# LPDDR4_SDRAM_-_1.net
KiCad netlist of a schematic drawn in Altium Designer
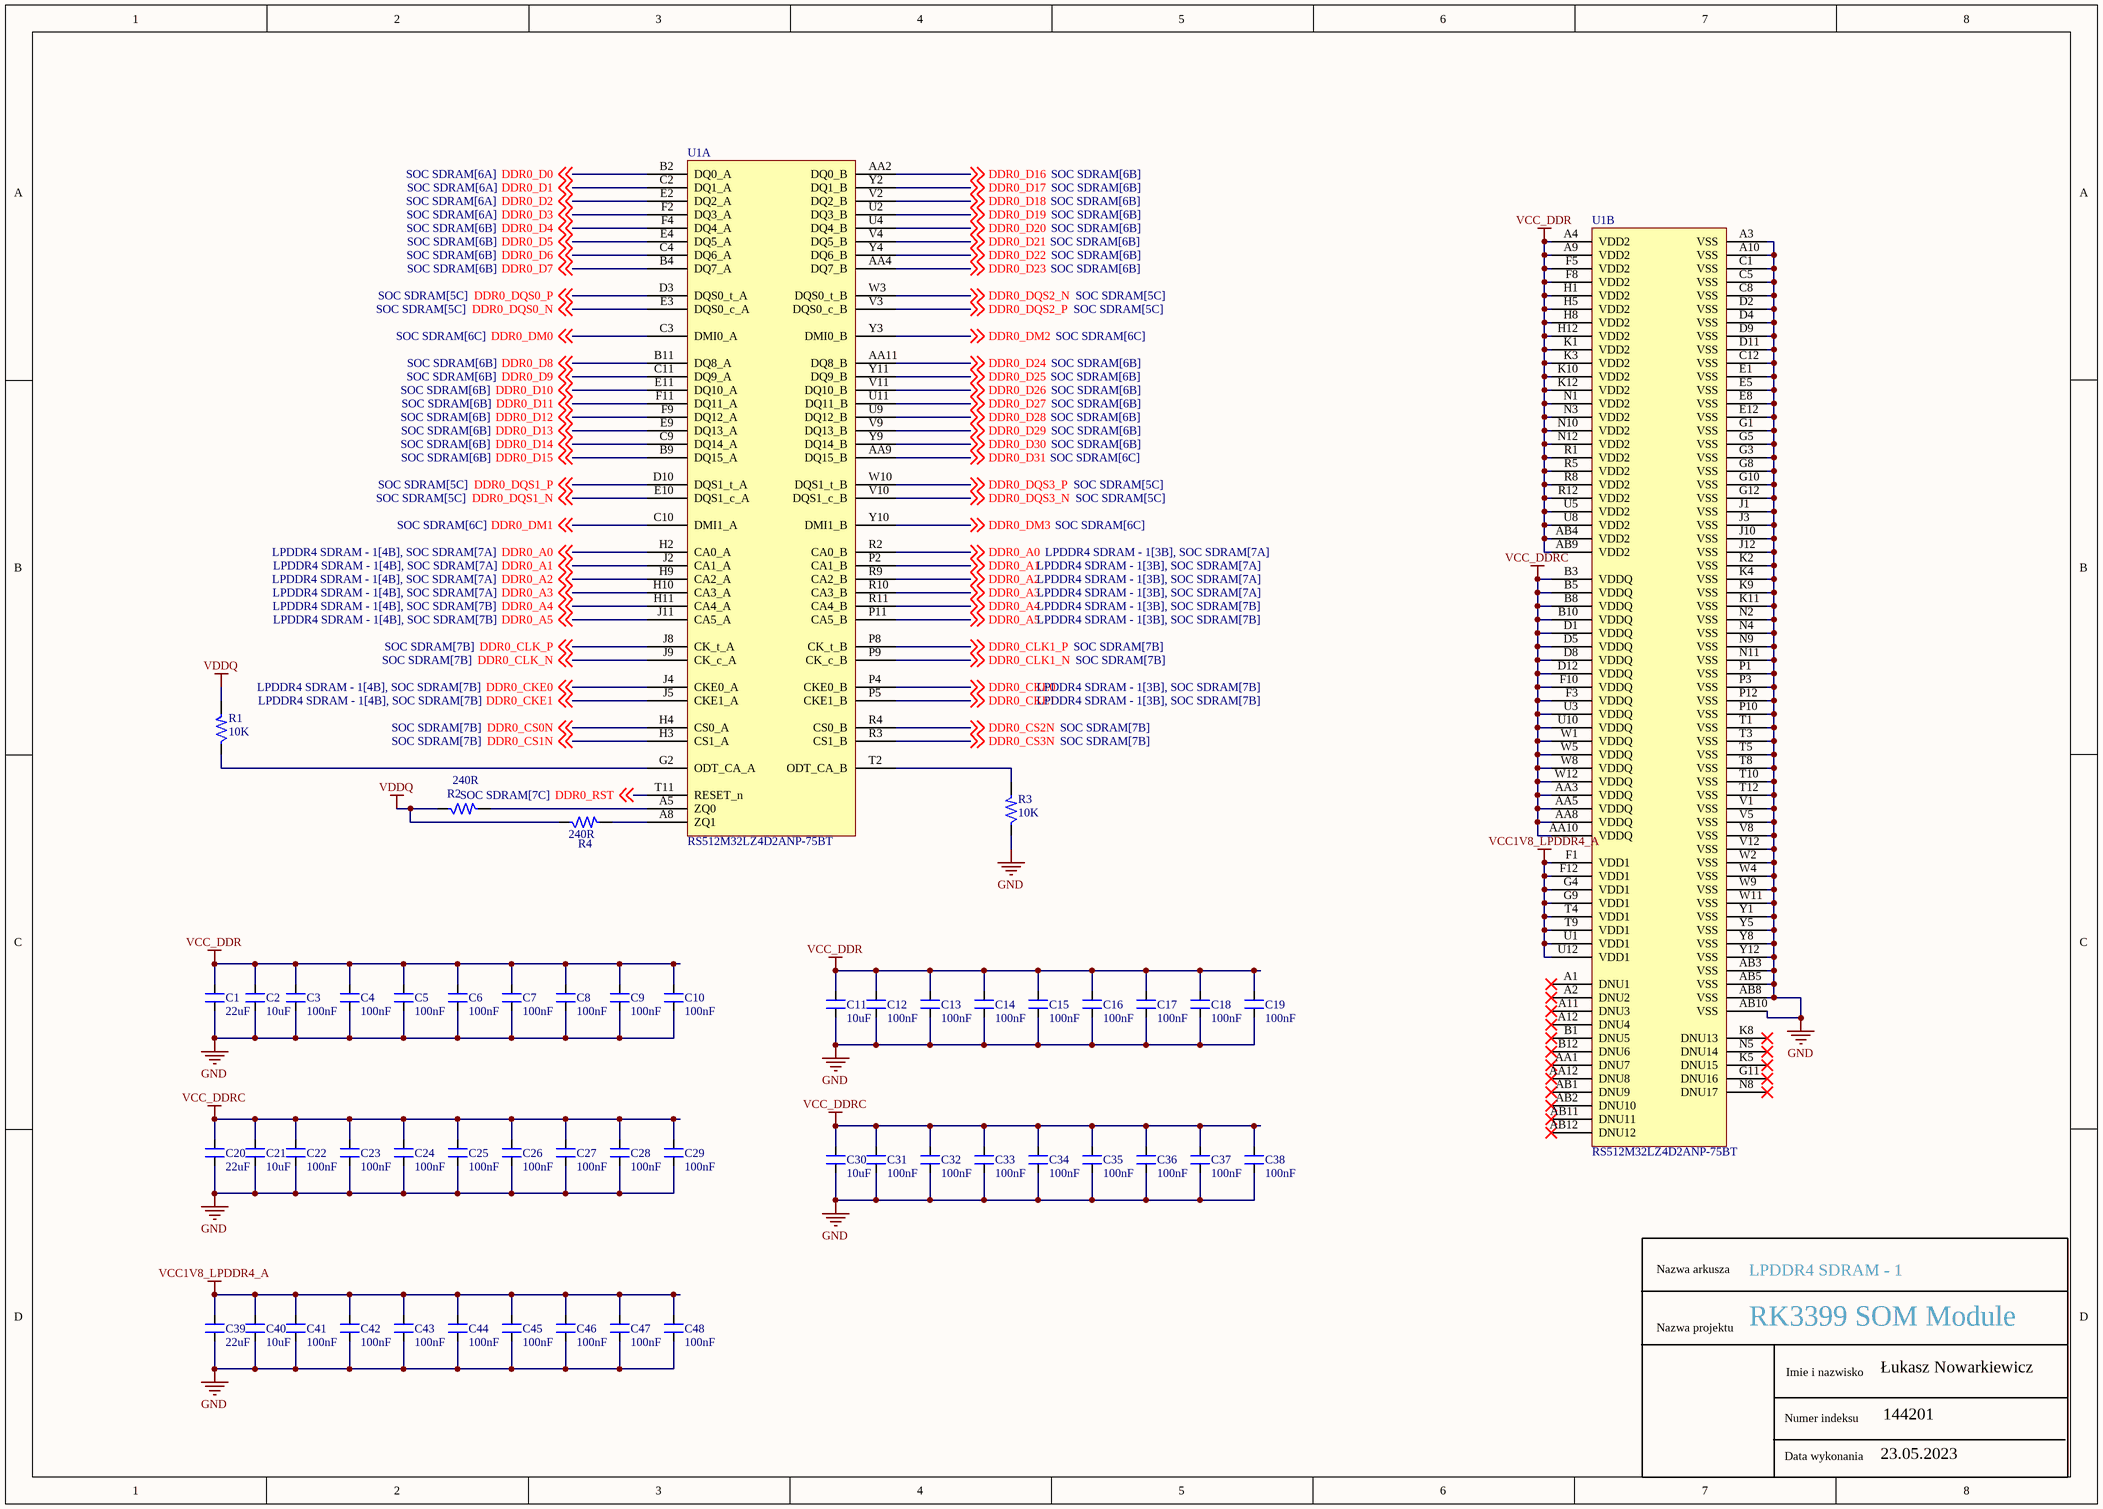
[diagram p0: LPDDR4 SDRAM - 1.SchDoc]

(export (version "E")
  (design (tool "Eeschema 10.0.6"))
  (components
    (comp (ref "C1")
      (value "22uF")
      (footprint "CAP_0603")
      (description "22µF ±20% 10V Ceramic Capacitor X5R 0603 (1608 Metric)")
      (fields
        (field (name "MANUFACTURER") "Murata Electronics")
        (field (name "MANUFACTURER PART NUMBER") "GRM188R61A226ME15D")
      )
      (libsource (lib "EsteemPCB_SOM_Course_intlib") (part "CAP_22uF-10V-20%-0603"))
    )
    (comp (ref "C2")
      (value "10uF")
      (footprint "CAP_0603")
      (description "10µF ±10% 10V Ceramic Capacitor X5R 0603 (1608 Metric)")
      (fields
        (field (name "MANUFACTURER PART NUMBER") "GRM188R61A106KE69J")
        (field (name "MANUFACTURER") "Murata Electronics")
      )
      (libsource (lib "EsteemPCB_SOM_Course_intlib") (part "CAP_10uF-10V-10%-0603"))
    )
    (comp (ref "C3")
      (value "100nF")
      (footprint "CAP_0402")
      (description "0.1µF ±10% 10V Ceramic Capacitor X7R 0402 (1005 Metric)")
      (fields
        (field (name "MANUFACTURER") "Yageo")
        (field (name "MANUFACTURER PART NUMBER") "CC0402KRX7R6BB104")
      )
      (libsource (lib "EsteemPCB_SOM_Course_intlib") (part "CAP_100nF-10V-10%-0402"))
    )
    (comp (ref "C4")
      (value "100nF")
      (footprint "CAP_0402")
      (description "0.1µF ±10% 10V Ceramic Capacitor X7R 0402 (1005 Metric)")
      (fields
        (field (name "MANUFACTURER") "Yageo")
        (field (name "MANUFACTURER PART NUMBER") "CC0402KRX7R6BB104")
      )
      (libsource (lib "EsteemPCB_SOM_Course_intlib") (part "CAP_100nF-10V-10%-0402"))
    )
    (comp (ref "C5")
      (value "100nF")
      (footprint "CAP_0402")
      (description "0.1µF ±10% 10V Ceramic Capacitor X7R 0402 (1005 Metric)")
      (fields
        (field (name "MANUFACTURER") "Yageo")
        (field (name "MANUFACTURER PART NUMBER") "CC0402KRX7R6BB104")
      )
      (libsource (lib "EsteemPCB_SOM_Course_intlib") (part "CAP_100nF-10V-10%-0402"))
    )
    (comp (ref "C6")
      (value "100nF")
      (footprint "CAP_0402")
      (description "0.1µF ±10% 10V Ceramic Capacitor X7R 0402 (1005 Metric)")
      (fields
        (field (name "MANUFACTURER") "Yageo")
        (field (name "MANUFACTURER PART NUMBER") "CC0402KRX7R6BB104")
      )
      (libsource (lib "EsteemPCB_SOM_Course_intlib") (part "CAP_100nF-10V-10%-0402"))
    )
    (comp (ref "C7")
      (value "100nF")
      (footprint "CAP_0402")
      (description "0.1µF ±10% 10V Ceramic Capacitor X7R 0402 (1005 Metric)")
      (fields
        (field (name "MANUFACTURER") "Yageo")
        (field (name "MANUFACTURER PART NUMBER") "CC0402KRX7R6BB104")
      )
      (libsource (lib "EsteemPCB_SOM_Course_intlib") (part "CAP_100nF-10V-10%-0402"))
    )
    (comp (ref "C8")
      (value "100nF")
      (footprint "CAP_0402")
      (description "0.1µF ±10% 10V Ceramic Capacitor X7R 0402 (1005 Metric)")
      (fields
        (field (name "MANUFACTURER") "Yageo")
        (field (name "MANUFACTURER PART NUMBER") "CC0402KRX7R6BB104")
      )
      (libsource (lib "EsteemPCB_SOM_Course_intlib") (part "CAP_100nF-10V-10%-0402"))
    )
    (comp (ref "C9")
      (value "100nF")
      (footprint "CAP_0402")
      (description "0.1µF ±10% 10V Ceramic Capacitor X7R 0402 (1005 Metric)")
      (fields
        (field (name "MANUFACTURER") "Yageo")
        (field (name "MANUFACTURER PART NUMBER") "CC0402KRX7R6BB104")
      )
      (libsource (lib "EsteemPCB_SOM_Course_intlib") (part "CAP_100nF-10V-10%-0402"))
    )
    (comp (ref "C10")
      (value "100nF")
      (footprint "CAP_0402")
      (description "0.1µF ±10% 10V Ceramic Capacitor X7R 0402 (1005 Metric)")
      (fields
        (field (name "MANUFACTURER") "Yageo")
        (field (name "MANUFACTURER PART NUMBER") "CC0402KRX7R6BB104")
      )
      (libsource (lib "EsteemPCB_SOM_Course_intlib") (part "CAP_100nF-10V-10%-0402"))
    )
    (comp (ref "C11")
      (value "10uF")
      (footprint "CAP_0603")
      (description "10µF ±10% 10V Ceramic Capacitor X5R 0603 (1608 Metric)")
      (fields
        (field (name "MANUFACTURER PART NUMBER") "GRM188R61A106KE69J")
        (field (name "MANUFACTURER") "Murata Electronics")
      )
      (libsource (lib "EsteemPCB_SOM_Course_intlib") (part "CAP_10uF-10V-10%-0603"))
    )
    (comp (ref "C12")
      (value "100nF")
      (footprint "CAP_0402")
      (description "0.1µF ±10% 10V Ceramic Capacitor X7R 0402 (1005 Metric)")
      (fields
        (field (name "MANUFACTURER") "Yageo")
        (field (name "MANUFACTURER PART NUMBER") "CC0402KRX7R6BB104")
      )
      (libsource (lib "EsteemPCB_SOM_Course_intlib") (part "CAP_100nF-10V-10%-0402"))
    )
    (comp (ref "C13")
      (value "100nF")
      (footprint "CAP_0402")
      (description "0.1µF ±10% 10V Ceramic Capacitor X7R 0402 (1005 Metric)")
      (fields
        (field (name "MANUFACTURER") "Yageo")
        (field (name "MANUFACTURER PART NUMBER") "CC0402KRX7R6BB104")
      )
      (libsource (lib "EsteemPCB_SOM_Course_intlib") (part "CAP_100nF-10V-10%-0402"))
    )
    (comp (ref "C14")
      (value "100nF")
      (footprint "CAP_0402")
      (description "0.1µF ±10% 10V Ceramic Capacitor X7R 0402 (1005 Metric)")
      (fields
        (field (name "MANUFACTURER") "Yageo")
        (field (name "MANUFACTURER PART NUMBER") "CC0402KRX7R6BB104")
      )
      (libsource (lib "EsteemPCB_SOM_Course_intlib") (part "CAP_100nF-10V-10%-0402"))
    )
    (comp (ref "C15")
      (value "100nF")
      (footprint "CAP_0402")
      (description "0.1µF ±10% 10V Ceramic Capacitor X7R 0402 (1005 Metric)")
      (fields
        (field (name "MANUFACTURER") "Yageo")
        (field (name "MANUFACTURER PART NUMBER") "CC0402KRX7R6BB104")
      )
      (libsource (lib "EsteemPCB_SOM_Course_intlib") (part "CAP_100nF-10V-10%-0402"))
    )
    (comp (ref "C16")
      (value "100nF")
      (footprint "CAP_0402")
      (description "0.1µF ±10% 10V Ceramic Capacitor X7R 0402 (1005 Metric)")
      (fields
        (field (name "MANUFACTURER") "Yageo")
        (field (name "MANUFACTURER PART NUMBER") "CC0402KRX7R6BB104")
      )
      (libsource (lib "EsteemPCB_SOM_Course_intlib") (part "CAP_100nF-10V-10%-0402"))
    )
    (comp (ref "C17")
      (value "100nF")
      (footprint "CAP_0402")
      (description "0.1µF ±10% 10V Ceramic Capacitor X7R 0402 (1005 Metric)")
      (fields
        (field (name "MANUFACTURER") "Yageo")
        (field (name "MANUFACTURER PART NUMBER") "CC0402KRX7R6BB104")
      )
      (libsource (lib "EsteemPCB_SOM_Course_intlib") (part "CAP_100nF-10V-10%-0402"))
    )
    (comp (ref "C18")
      (value "100nF")
      (footprint "CAP_0402")
      (description "0.1µF ±10% 10V Ceramic Capacitor X7R 0402 (1005 Metric)")
      (fields
        (field (name "MANUFACTURER") "Yageo")
        (field (name "MANUFACTURER PART NUMBER") "CC0402KRX7R6BB104")
      )
      (libsource (lib "EsteemPCB_SOM_Course_intlib") (part "CAP_100nF-10V-10%-0402"))
    )
    (comp (ref "C19")
      (value "100nF")
      (footprint "CAP_0402")
      (description "0.1µF ±10% 10V Ceramic Capacitor X7R 0402 (1005 Metric)")
      (fields
        (field (name "MANUFACTURER") "Yageo")
        (field (name "MANUFACTURER PART NUMBER") "CC0402KRX7R6BB104")
      )
      (libsource (lib "EsteemPCB_SOM_Course_intlib") (part "CAP_100nF-10V-10%-0402"))
    )
    (comp (ref "C20")
      (value "22uF")
      (footprint "CAP_0603")
      (description "22µF ±20% 10V Ceramic Capacitor X5R 0603 (1608 Metric)")
      (fields
        (field (name "MANUFACTURER") "Murata Electronics")
        (field (name "MANUFACTURER PART NUMBER") "GRM188R61A226ME15D")
      )
      (libsource (lib "EsteemPCB_SOM_Course_intlib") (part "CAP_22uF-10V-20%-0603"))
    )
    (comp (ref "C21")
      (value "10uF")
      (footprint "CAP_0603")
      (description "10µF ±10% 10V Ceramic Capacitor X5R 0603 (1608 Metric)")
      (fields
        (field (name "MANUFACTURER PART NUMBER") "GRM188R61A106KE69J")
        (field (name "MANUFACTURER") "Murata Electronics")
      )
      (libsource (lib "EsteemPCB_SOM_Course_intlib") (part "CAP_10uF-10V-10%-0603"))
    )
    (comp (ref "C22")
      (value "100nF")
      (footprint "CAP_0402")
      (description "0.1µF ±10% 10V Ceramic Capacitor X7R 0402 (1005 Metric)")
      (fields
        (field (name "MANUFACTURER") "Yageo")
        (field (name "MANUFACTURER PART NUMBER") "CC0402KRX7R6BB104")
      )
      (libsource (lib "EsteemPCB_SOM_Course_intlib") (part "CAP_100nF-10V-10%-0402"))
    )
    (comp (ref "C23")
      (value "100nF")
      (footprint "CAP_0402")
      (description "0.1µF ±10% 10V Ceramic Capacitor X7R 0402 (1005 Metric)")
      (fields
        (field (name "MANUFACTURER") "Yageo")
        (field (name "MANUFACTURER PART NUMBER") "CC0402KRX7R6BB104")
      )
      (libsource (lib "EsteemPCB_SOM_Course_intlib") (part "CAP_100nF-10V-10%-0402"))
    )
    (comp (ref "C24")
      (value "100nF")
      (footprint "CAP_0402")
      (description "0.1µF ±10% 10V Ceramic Capacitor X7R 0402 (1005 Metric)")
      (fields
        (field (name "MANUFACTURER") "Yageo")
        (field (name "MANUFACTURER PART NUMBER") "CC0402KRX7R6BB104")
      )
      (libsource (lib "EsteemPCB_SOM_Course_intlib") (part "CAP_100nF-10V-10%-0402"))
    )
    (comp (ref "C25")
      (value "100nF")
      (footprint "CAP_0402")
      (description "0.1µF ±10% 10V Ceramic Capacitor X7R 0402 (1005 Metric)")
      (fields
        (field (name "MANUFACTURER") "Yageo")
        (field (name "MANUFACTURER PART NUMBER") "CC0402KRX7R6BB104")
      )
      (libsource (lib "EsteemPCB_SOM_Course_intlib") (part "CAP_100nF-10V-10%-0402"))
    )
    (comp (ref "C26")
      (value "100nF")
      (footprint "CAP_0402")
      (description "0.1µF ±10% 10V Ceramic Capacitor X7R 0402 (1005 Metric)")
      (fields
        (field (name "MANUFACTURER") "Yageo")
        (field (name "MANUFACTURER PART NUMBER") "CC0402KRX7R6BB104")
      )
      (libsource (lib "EsteemPCB_SOM_Course_intlib") (part "CAP_100nF-10V-10%-0402"))
    )
    (comp (ref "C27")
      (value "100nF")
      (footprint "CAP_0402")
      (description "0.1µF ±10% 10V Ceramic Capacitor X7R 0402 (1005 Metric)")
      (fields
        (field (name "MANUFACTURER") "Yageo")
        (field (name "MANUFACTURER PART NUMBER") "CC0402KRX7R6BB104")
      )
      (libsource (lib "EsteemPCB_SOM_Course_intlib") (part "CAP_100nF-10V-10%-0402"))
    )
    (comp (ref "C28")
      (value "100nF")
      (footprint "CAP_0402")
      (description "0.1µF ±10% 10V Ceramic Capacitor X7R 0402 (1005 Metric)")
      (fields
        (field (name "MANUFACTURER") "Yageo")
        (field (name "MANUFACTURER PART NUMBER") "CC0402KRX7R6BB104")
      )
      (libsource (lib "EsteemPCB_SOM_Course_intlib") (part "CAP_100nF-10V-10%-0402"))
    )
    (comp (ref "C29")
      (value "100nF")
      (footprint "CAP_0402")
      (description "0.1µF ±10% 10V Ceramic Capacitor X7R 0402 (1005 Metric)")
      (fields
        (field (name "MANUFACTURER") "Yageo")
        (field (name "MANUFACTURER PART NUMBER") "CC0402KRX7R6BB104")
      )
      (libsource (lib "EsteemPCB_SOM_Course_intlib") (part "CAP_100nF-10V-10%-0402"))
    )
    (comp (ref "C30")
      (value "10uF")
      (footprint "CAP_0603")
      (description "10µF ±10% 10V Ceramic Capacitor X5R 0603 (1608 Metric)")
      (fields
        (field (name "MANUFACTURER PART NUMBER") "GRM188R61A106KE69J")
        (field (name "MANUFACTURER") "Murata Electronics")
      )
      (libsource (lib "EsteemPCB_SOM_Course_intlib") (part "CAP_10uF-10V-10%-0603"))
    )
    (comp (ref "C31")
      (value "100nF")
      (footprint "CAP_0402")
      (description "0.1µF ±10% 10V Ceramic Capacitor X7R 0402 (1005 Metric)")
      (fields
        (field (name "MANUFACTURER") "Yageo")
        (field (name "MANUFACTURER PART NUMBER") "CC0402KRX7R6BB104")
      )
      (libsource (lib "EsteemPCB_SOM_Course_intlib") (part "CAP_100nF-10V-10%-0402"))
    )
    (comp (ref "C32")
      (value "100nF")
      (footprint "CAP_0402")
      (description "0.1µF ±10% 10V Ceramic Capacitor X7R 0402 (1005 Metric)")
      (fields
        (field (name "MANUFACTURER") "Yageo")
        (field (name "MANUFACTURER PART NUMBER") "CC0402KRX7R6BB104")
      )
      (libsource (lib "EsteemPCB_SOM_Course_intlib") (part "CAP_100nF-10V-10%-0402"))
    )
    (comp (ref "C33")
      (value "100nF")
      (footprint "CAP_0402")
      (description "0.1µF ±10% 10V Ceramic Capacitor X7R 0402 (1005 Metric)")
      (fields
        (field (name "MANUFACTURER") "Yageo")
        (field (name "MANUFACTURER PART NUMBER") "CC0402KRX7R6BB104")
      )
      (libsource (lib "EsteemPCB_SOM_Course_intlib") (part "CAP_100nF-10V-10%-0402"))
    )
    (comp (ref "C34")
      (value "100nF")
      (footprint "CAP_0402")
      (description "0.1µF ±10% 10V Ceramic Capacitor X7R 0402 (1005 Metric)")
      (fields
        (field (name "MANUFACTURER") "Yageo")
        (field (name "MANUFACTURER PART NUMBER") "CC0402KRX7R6BB104")
      )
      (libsource (lib "EsteemPCB_SOM_Course_intlib") (part "CAP_100nF-10V-10%-0402"))
    )
    (comp (ref "C35")
      (value "100nF")
      (footprint "CAP_0402")
      (description "0.1µF ±10% 10V Ceramic Capacitor X7R 0402 (1005 Metric)")
      (fields
        (field (name "MANUFACTURER") "Yageo")
        (field (name "MANUFACTURER PART NUMBER") "CC0402KRX7R6BB104")
      )
      (libsource (lib "EsteemPCB_SOM_Course_intlib") (part "CAP_100nF-10V-10%-0402"))
    )
    (comp (ref "C36")
      (value "100nF")
      (footprint "CAP_0402")
      (description "0.1µF ±10% 10V Ceramic Capacitor X7R 0402 (1005 Metric)")
      (fields
        (field (name "MANUFACTURER") "Yageo")
        (field (name "MANUFACTURER PART NUMBER") "CC0402KRX7R6BB104")
      )
      (libsource (lib "EsteemPCB_SOM_Course_intlib") (part "CAP_100nF-10V-10%-0402"))
    )
    (comp (ref "C37")
      (value "100nF")
      (footprint "CAP_0402")
      (description "0.1µF ±10% 10V Ceramic Capacitor X7R 0402 (1005 Metric)")
      (fields
        (field (name "MANUFACTURER") "Yageo")
        (field (name "MANUFACTURER PART NUMBER") "CC0402KRX7R6BB104")
      )
      (libsource (lib "EsteemPCB_SOM_Course_intlib") (part "CAP_100nF-10V-10%-0402"))
    )
    (comp (ref "C38")
      (value "100nF")
      (footprint "CAP_0402")
      (description "0.1µF ±10% 10V Ceramic Capacitor X7R 0402 (1005 Metric)")
      (fields
        (field (name "MANUFACTURER") "Yageo")
        (field (name "MANUFACTURER PART NUMBER") "CC0402KRX7R6BB104")
      )
      (libsource (lib "EsteemPCB_SOM_Course_intlib") (part "CAP_100nF-10V-10%-0402"))
    )
    (comp (ref "C39")
      (value "22uF")
      (footprint "CAP_0603")
      (description "22µF ±20% 10V Ceramic Capacitor X5R 0603 (1608 Metric)")
      (fields
        (field (name "MANUFACTURER") "Murata Electronics")
        (field (name "MANUFACTURER PART NUMBER") "GRM188R61A226ME15D")
      )
      (libsource (lib "EsteemPCB_SOM_Course_intlib") (part "CAP_22uF-10V-20%-0603"))
    )
    (comp (ref "C40")
      (value "10uF")
      (footprint "CAP_0603")
      (description "10µF ±10% 10V Ceramic Capacitor X5R 0603 (1608 Metric)")
      (fields
        (field (name "MANUFACTURER PART NUMBER") "GRM188R61A106KE69J")
        (field (name "MANUFACTURER") "Murata Electronics")
      )
      (libsource (lib "EsteemPCB_SOM_Course_intlib") (part "CAP_10uF-10V-10%-0603"))
    )
    (comp (ref "C41")
      (value "100nF")
      (footprint "CAP_0402")
      (description "0.1µF ±10% 10V Ceramic Capacitor X7R 0402 (1005 Metric)")
      (fields
        (field (name "MANUFACTURER") "Yageo")
        (field (name "MANUFACTURER PART NUMBER") "CC0402KRX7R6BB104")
      )
      (libsource (lib "EsteemPCB_SOM_Course_intlib") (part "CAP_100nF-10V-10%-0402"))
    )
    (comp (ref "C42")
      (value "100nF")
      (footprint "CAP_0402")
      (description "0.1µF ±10% 10V Ceramic Capacitor X7R 0402 (1005 Metric)")
      (fields
        (field (name "MANUFACTURER") "Yageo")
        (field (name "MANUFACTURER PART NUMBER") "CC0402KRX7R6BB104")
      )
      (libsource (lib "EsteemPCB_SOM_Course_intlib") (part "CAP_100nF-10V-10%-0402"))
    )
    (comp (ref "C43")
      (value "100nF")
      (footprint "CAP_0402")
      (description "0.1µF ±10% 10V Ceramic Capacitor X7R 0402 (1005 Metric)")
      (fields
        (field (name "MANUFACTURER") "Yageo")
        (field (name "MANUFACTURER PART NUMBER") "CC0402KRX7R6BB104")
      )
      (libsource (lib "EsteemPCB_SOM_Course_intlib") (part "CAP_100nF-10V-10%-0402"))
    )
    (comp (ref "C44")
      (value "100nF")
      (footprint "CAP_0402")
      (description "0.1µF ±10% 10V Ceramic Capacitor X7R 0402 (1005 Metric)")
      (fields
        (field (name "MANUFACTURER") "Yageo")
        (field (name "MANUFACTURER PART NUMBER") "CC0402KRX7R6BB104")
      )
      (libsource (lib "EsteemPCB_SOM_Course_intlib") (part "CAP_100nF-10V-10%-0402"))
    )
    (comp (ref "C45")
      (value "100nF")
      (footprint "CAP_0402")
      (description "0.1µF ±10% 10V Ceramic Capacitor X7R 0402 (1005 Metric)")
      (fields
        (field (name "MANUFACTURER") "Yageo")
        (field (name "MANUFACTURER PART NUMBER") "CC0402KRX7R6BB104")
      )
      (libsource (lib "EsteemPCB_SOM_Course_intlib") (part "CAP_100nF-10V-10%-0402"))
    )
    (comp (ref "C46")
      (value "100nF")
      (footprint "CAP_0402")
      (description "0.1µF ±10% 10V Ceramic Capacitor X7R 0402 (1005 Metric)")
      (fields
        (field (name "MANUFACTURER") "Yageo")
        (field (name "MANUFACTURER PART NUMBER") "CC0402KRX7R6BB104")
      )
      (libsource (lib "EsteemPCB_SOM_Course_intlib") (part "CAP_100nF-10V-10%-0402"))
    )
    (comp (ref "C47")
      (value "100nF")
      (footprint "CAP_0402")
      (description "0.1µF ±10% 10V Ceramic Capacitor X7R 0402 (1005 Metric)")
      (fields
        (field (name "MANUFACTURER") "Yageo")
        (field (name "MANUFACTURER PART NUMBER") "CC0402KRX7R6BB104")
      )
      (libsource (lib "EsteemPCB_SOM_Course_intlib") (part "CAP_100nF-10V-10%-0402"))
    )
    (comp (ref "C48")
      (value "100nF")
      (footprint "CAP_0402")
      (description "0.1µF ±10% 10V Ceramic Capacitor X7R 0402 (1005 Metric)")
      (fields
        (field (name "MANUFACTURER") "Yageo")
        (field (name "MANUFACTURER PART NUMBER") "CC0402KRX7R6BB104")
      )
      (libsource (lib "EsteemPCB_SOM_Course_intlib") (part "CAP_100nF-10V-10%-0402"))
    )
    (comp (ref "R1")
      (value "10K")
      (footprint "RES_0201")
      (description "10 kOhms ±1% 0.05W, 1/20W Chip Resistor 0201 (0603 Metric) Thick Film")
      (fields
        (field (name "MANUFACTURER") "Stackpole Electronics Inc")
        (field (name "MANUFACTURER PART NUMBER") "RMCF0201FT10K0")
      )
      (libsource (lib "EsteemPCB_SOM_Course_intlib") (part "RES_10K-0.05W-1%-0201"))
    )
    (comp (ref "R2")
      (value "240R")
      (footprint "RES_0201")
      (description "240 Ohms ±1% 0.05W, 1/20W Chip Resistor 0201 (0603 Metric) Thick Film")
      (fields
        (field (name "MANUFACTURER") "Yageo")
        (field (name "MANUFACTURER PART NUMBER") "RC0201FR-07240RL")
      )
      (libsource (lib "EsteemPCB_SOM_Course_intlib") (part "RES_240R-0.05W-1%-0201"))
    )
    (comp (ref "R3")
      (value "10K")
      (footprint "RES_0201")
      (description "10 kOhms ±1% 0.05W, 1/20W Chip Resistor 0201 (0603 Metric) Thick Film")
      (fields
        (field (name "MANUFACTURER") "Stackpole Electronics Inc")
        (field (name "MANUFACTURER PART NUMBER") "RMCF0201FT10K0")
      )
      (libsource (lib "EsteemPCB_SOM_Course_intlib") (part "RES_10K-0.05W-1%-0201"))
    )
    (comp (ref "R4")
      (value "240R")
      (footprint "RES_0201")
      (description "240 Ohms ±1% 0.05W, 1/20W Chip Resistor 0201 (0603 Metric) Thick Film")
      (fields
        (field (name "MANUFACTURER") "Yageo")
        (field (name "MANUFACTURER PART NUMBER") "RC0201FR-07240RL")
      )
      (libsource (lib "EsteemPCB_SOM_Course_intlib") (part "RES_240R-0.05W-1%-0201"))
    )
    (comp (ref "U1")
      (value "RS512M32LZ4D2ANP-75BT")
      (footprint "FBGA200_SMD")
      (fields (field (name "MANUFACTURER") "RAYSON"))
      (libsource (lib "EsteemPCB_SOM_Course_intlib") (part "IC_RS512M32LZ4D2ANP-75BT"))
    )
  )
  (nets
    (net (code "1") (name "DDR0_A0") (class "Default")
      (node (ref "U1") (pin "H2") (pinfunction "CA0_A_H2") (pintype "passive"))
      (node (ref "U1") (pin "R2") (pinfunction "CA0_B_R2") (pintype "passive"))
    )
    (net (code "2") (name "DDR0_A1") (class "Default")
      (node (ref "U1") (pin "J2") (pinfunction "CA1_A_J2") (pintype "passive"))
      (node (ref "U1") (pin "P2") (pinfunction "CA1_B_P2") (pintype "passive"))
    )
    (net (code "3") (name "DDR0_A2") (class "Default")
      (node (ref "U1") (pin "H9") (pinfunction "CA2_A_H9") (pintype "passive"))
      (node (ref "U1") (pin "R9") (pinfunction "CA2_B_R9") (pintype "passive"))
    )
    (net (code "4") (name "DDR0_A3") (class "Default")
      (node (ref "U1") (pin "H10") (pinfunction "CA3_A_H10") (pintype "passive"))
      (node (ref "U1") (pin "R10") (pinfunction "CA3_B_R10") (pintype "passive"))
    )
    (net (code "5") (name "DDR0_A4") (class "Default")
      (node (ref "U1") (pin "H11") (pinfunction "CA4_A_H11") (pintype "passive"))
      (node (ref "U1") (pin "R11") (pinfunction "CA4_B_R11") (pintype "passive"))
    )
    (net (code "6") (name "DDR0_A5") (class "Default")
      (node (ref "U1") (pin "J11") (pinfunction "CA5_A_J11") (pintype "passive"))
      (node (ref "U1") (pin "P11") (pinfunction "CA5_B_P11") (pintype "passive"))
    )
    (net (code "7") (name "DDR0_CKE0") (class "Default")
      (node (ref "U1") (pin "J4") (pinfunction "CKE0_A_J4") (pintype "passive"))
      (node (ref "U1") (pin "P4") (pinfunction "CKE0_B_P4") (pintype "passive"))
    )
    (net (code "8") (name "DDR0_CKE1") (class "Default")
      (node (ref "U1") (pin "J5") (pinfunction "CKE1_A_J5") (pintype "passive"))
      (node (ref "U1") (pin "P5") (pinfunction "CKE1_B_P5") (pintype "passive"))
    )
    (net (code "9") (name "DDR0_CLK1_N") (class "Default")
      (node (ref "U1") (pin "P9") (pinfunction "CK_c_B_P9") (pintype "passive"))
    )
    (net (code "10") (name "DDR0_CLK1_P") (class "Default")
      (node (ref "U1") (pin "P8") (pinfunction "CK_t_B_P8") (pintype "passive"))
    )
    (net (code "11") (name "DDR0_CLK_N") (class "Default")
      (node (ref "U1") (pin "J9") (pinfunction "CK_c_A_J9") (pintype "passive"))
    )
    (net (code "12") (name "DDR0_CLK_P") (class "Default")
      (node (ref "U1") (pin "J8") (pinfunction "CK_t_A_J8") (pintype "passive"))
    )
    (net (code "13") (name "DDR0_CS0N") (class "Default")
      (node (ref "U1") (pin "H4") (pinfunction "CS0_A_H4") (pintype "passive"))
    )
    (net (code "14") (name "DDR0_CS1N") (class "Default")
      (node (ref "U1") (pin "H3") (pinfunction "CS1_A_H3") (pintype "passive"))
    )
    (net (code "15") (name "DDR0_CS2N") (class "Default")
      (node (ref "U1") (pin "R4") (pinfunction "CS0_B_R4") (pintype "passive"))
    )
    (net (code "16") (name "DDR0_CS3N") (class "Default")
      (node (ref "U1") (pin "R3") (pinfunction "CS1_B_R3") (pintype "passive"))
    )
    (net (code "17") (name "DDR0_D0") (class "Default")
      (node (ref "U1") (pin "B2") (pinfunction "DQ0_A_B2") (pintype "passive"))
    )
    (net (code "18") (name "DDR0_D1") (class "Default")
      (node (ref "U1") (pin "C2") (pinfunction "DQ1_A_C2") (pintype "passive"))
    )
    (net (code "19") (name "DDR0_D2") (class "Default")
      (node (ref "U1") (pin "E2") (pinfunction "DQ2_A_E2") (pintype "passive"))
    )
    (net (code "20") (name "DDR0_D3") (class "Default")
      (node (ref "U1") (pin "F2") (pinfunction "DQ3_A_F2") (pintype "passive"))
    )
    (net (code "21") (name "DDR0_D4") (class "Default")
      (node (ref "U1") (pin "F4") (pinfunction "DQ4_A_F4") (pintype "passive"))
    )
    (net (code "22") (name "DDR0_D5") (class "Default")
      (node (ref "U1") (pin "E4") (pinfunction "DQ5_A_E4") (pintype "passive"))
    )
    (net (code "23") (name "DDR0_D6") (class "Default")
      (node (ref "U1") (pin "C4") (pinfunction "DQ6_A_C4") (pintype "passive"))
    )
    (net (code "24") (name "DDR0_D7") (class "Default")
      (node (ref "U1") (pin "B4") (pinfunction "DQ7_A_B4") (pintype "passive"))
    )
    (net (code "25") (name "DDR0_D8") (class "Default")
      (node (ref "U1") (pin "B11") (pinfunction "DQ8_A_B11") (pintype "passive"))
    )
    (net (code "26") (name "DDR0_D9") (class "Default")
      (node (ref "U1") (pin "C11") (pinfunction "DQ9_A_C11") (pintype "passive"))
    )
    (net (code "27") (name "DDR0_D10") (class "Default")
      (node (ref "U1") (pin "E11") (pinfunction "DQ10_A_E11") (pintype "passive"))
    )
    (net (code "28") (name "DDR0_D11") (class "Default")
      (node (ref "U1") (pin "F11") (pinfunction "DQ11_A_F11") (pintype "passive"))
    )
    (net (code "29") (name "DDR0_D12") (class "Default")
      (node (ref "U1") (pin "F9") (pinfunction "DQ12_A_F9") (pintype "passive"))
    )
    (net (code "30") (name "DDR0_D13") (class "Default")
      (node (ref "U1") (pin "E9") (pinfunction "DQ13_A_E9") (pintype "passive"))
    )
    (net (code "31") (name "DDR0_D14") (class "Default")
      (node (ref "U1") (pin "C9") (pinfunction "DQ14_A_C9") (pintype "passive"))
    )
    (net (code "32") (name "DDR0_D15") (class "Default")
      (node (ref "U1") (pin "B9") (pinfunction "DQ15_A_B9") (pintype "passive"))
    )
    (net (code "33") (name "DDR0_D16") (class "Default")
      (node (ref "U1") (pin "AA2") (pinfunction "DQ0_B_AA2") (pintype "passive"))
    )
    (net (code "34") (name "DDR0_D17") (class "Default")
      (node (ref "U1") (pin "Y2") (pinfunction "DQ1_B_Y2") (pintype "passive"))
    )
    (net (code "35") (name "DDR0_D18") (class "Default")
      (node (ref "U1") (pin "V2") (pinfunction "DQ2_B_V2") (pintype "passive"))
    )
    (net (code "36") (name "DDR0_D19") (class "Default")
      (node (ref "U1") (pin "U2") (pinfunction "DQ3_B_U2") (pintype "passive"))
    )
    (net (code "37") (name "DDR0_D20") (class "Default")
      (node (ref "U1") (pin "U4") (pinfunction "DQ4_B_U4") (pintype "passive"))
    )
    (net (code "38") (name "DDR0_D21") (class "Default")
      (node (ref "U1") (pin "V4") (pinfunction "DQ5_B_V4") (pintype "passive"))
    )
    (net (code "39") (name "DDR0_D22") (class "Default")
      (node (ref "U1") (pin "Y4") (pinfunction "DQ6_B_Y4") (pintype "passive"))
    )
    (net (code "40") (name "DDR0_D23") (class "Default")
      (node (ref "U1") (pin "AA4") (pinfunction "DQ7_B_AA4") (pintype "passive"))
    )
    (net (code "41") (name "DDR0_D24") (class "Default")
      (node (ref "U1") (pin "AA11") (pinfunction "DQ8_B_AA11") (pintype "passive"))
    )
    (net (code "42") (name "DDR0_D25") (class "Default")
      (node (ref "U1") (pin "Y11") (pinfunction "DQ9_B_Y11") (pintype "passive"))
    )
    (net (code "43") (name "DDR0_D26") (class "Default")
      (node (ref "U1") (pin "V11") (pinfunction "DQ10_B_V11") (pintype "passive"))
    )
    (net (code "44") (name "DDR0_D27") (class "Default")
      (node (ref "U1") (pin "U11") (pinfunction "DQ11_B_U11") (pintype "passive"))
    )
    (net (code "45") (name "DDR0_D28") (class "Default")
      (node (ref "U1") (pin "U9") (pinfunction "DQ12_B_U9") (pintype "passive"))
    )
    (net (code "46") (name "DDR0_D29") (class "Default")
      (node (ref "U1") (pin "V9") (pinfunction "DQ13_B_V9") (pintype "passive"))
    )
    (net (code "47") (name "DDR0_D30") (class "Default")
      (node (ref "U1") (pin "Y9") (pinfunction "DQ14_B_Y9") (pintype "passive"))
    )
    (net (code "48") (name "DDR0_D31") (class "Default")
      (node (ref "U1") (pin "AA9") (pinfunction "DQ15_B_AA9") (pintype "passive"))
    )
    (net (code "49") (name "DDR0_DM0") (class "Default")
      (node (ref "U1") (pin "C3") (pinfunction "DMI0_A_C3") (pintype "passive"))
    )
    (net (code "50") (name "DDR0_DM1") (class "Default")
      (node (ref "U1") (pin "C10") (pinfunction "DMI1_A_C10") (pintype "passive"))
    )
    (net (code "51") (name "DDR0_DM2") (class "Default")
      (node (ref "U1") (pin "Y3") (pinfunction "DMI0_B_Y3") (pintype "passive"))
    )
    (net (code "52") (name "DDR0_DM3") (class "Default")
      (node (ref "U1") (pin "Y10") (pinfunction "DMI1_B_Y10") (pintype "passive"))
    )
    (net (code "53") (name "DDR0_DQS0_N") (class "Default")
      (node (ref "U1") (pin "E3") (pinfunction "DQS0_c_A_E3") (pintype "passive"))
    )
    (net (code "54") (name "DDR0_DQS0_P") (class "Default")
      (node (ref "U1") (pin "D3") (pinfunction "DQS0_t_A_D3") (pintype "passive"))
    )
    (net (code "55") (name "DDR0_DQS1_N") (class "Default")
      (node (ref "U1") (pin "E10") (pinfunction "DQS1_c_A_E10") (pintype "passive"))
    )
    (net (code "56") (name "DDR0_DQS1_P") (class "Default")
      (node (ref "U1") (pin "D10") (pinfunction "DQS1_t_A_D10") (pintype "passive"))
    )
    (net (code "57") (name "DDR0_DQS2_N") (class "Default")
      (node (ref "U1") (pin "W3") (pinfunction "DQS0_t_B_W3") (pintype "passive"))
    )
    (net (code "58") (name "DDR0_DQS2_P") (class "Default")
      (node (ref "U1") (pin "V3") (pinfunction "DQS0_c_B_V3") (pintype "passive"))
    )
    (net (code "59") (name "DDR0_DQS3_N") (class "Default")
      (node (ref "U1") (pin "V10") (pinfunction "DQS1_c_B_V10") (pintype "passive"))
    )
    (net (code "60") (name "DDR0_DQS3_P") (class "Default")
      (node (ref "U1") (pin "W10") (pinfunction "DQS1_t_B_W10") (pintype "passive"))
    )
    (net (code "61") (name "DDR0_RST") (class "Default")
      (node (ref "U1") (pin "T11") (pinfunction "RESET_n_T11") (pintype "passive"))
    )
    (net (code "62") (name "GND") (class "Default")
      (node (ref "C1") (pin "1") (pinfunction "1_1") (pintype "passive"))
      (node (ref "C10") (pin "1") (pinfunction "1_1") (pintype "passive"))
      (node (ref "C11") (pin "1") (pinfunction "1_1") (pintype "passive"))
      (node (ref "C12") (pin "1") (pinfunction "1_1") (pintype "passive"))
      (node (ref "C13") (pin "1") (pinfunction "1_1") (pintype "passive"))
      (node (ref "C14") (pin "1") (pinfunction "1_1") (pintype "passive"))
      (node (ref "C15") (pin "1") (pinfunction "1_1") (pintype "passive"))
      (node (ref "C16") (pin "1") (pinfunction "1_1") (pintype "passive"))
      (node (ref "C17") (pin "1") (pinfunction "1_1") (pintype "passive"))
      (node (ref "C18") (pin "1") (pinfunction "1_1") (pintype "passive"))
      (node (ref "C19") (pin "1") (pinfunction "1_1") (pintype "passive"))
      (node (ref "C2") (pin "1") (pinfunction "1_1") (pintype "passive"))
      (node (ref "C20") (pin "1") (pinfunction "1_1") (pintype "passive"))
      (node (ref "C21") (pin "1") (pinfunction "1_1") (pintype "passive"))
      (node (ref "C22") (pin "1") (pinfunction "1_1") (pintype "passive"))
      (node (ref "C23") (pin "1") (pinfunction "1_1") (pintype "passive"))
      (node (ref "C24") (pin "1") (pinfunction "1_1") (pintype "passive"))
      (node (ref "C25") (pin "1") (pinfunction "1_1") (pintype "passive"))
      (node (ref "C26") (pin "1") (pinfunction "1_1") (pintype "passive"))
      (node (ref "C27") (pin "1") (pinfunction "1_1") (pintype "passive"))
      (node (ref "C28") (pin "1") (pinfunction "1_1") (pintype "passive"))
      (node (ref "C29") (pin "1") (pinfunction "1_1") (pintype "passive"))
      (node (ref "C3") (pin "1") (pinfunction "1_1") (pintype "passive"))
      (node (ref "C30") (pin "1") (pinfunction "1_1") (pintype "passive"))
      (node (ref "C31") (pin "1") (pinfunction "1_1") (pintype "passive"))
      (node (ref "C32") (pin "1") (pinfunction "1_1") (pintype "passive"))
      (node (ref "C33") (pin "1") (pinfunction "1_1") (pintype "passive"))
      (node (ref "C34") (pin "1") (pinfunction "1_1") (pintype "passive"))
      (node (ref "C35") (pin "1") (pinfunction "1_1") (pintype "passive"))
      (node (ref "C36") (pin "1") (pinfunction "1_1") (pintype "passive"))
      (node (ref "C37") (pin "1") (pinfunction "1_1") (pintype "passive"))
      (node (ref "C38") (pin "1") (pinfunction "1_1") (pintype "passive"))
      (node (ref "C39") (pin "1") (pinfunction "1_1") (pintype "passive"))
      (node (ref "C4") (pin "1") (pinfunction "1_1") (pintype "passive"))
      (node (ref "C40") (pin "1") (pinfunction "1_1") (pintype "passive"))
      (node (ref "C41") (pin "1") (pinfunction "1_1") (pintype "passive"))
      (node (ref "C42") (pin "1") (pinfunction "1_1") (pintype "passive"))
      (node (ref "C43") (pin "1") (pinfunction "1_1") (pintype "passive"))
      (node (ref "C44") (pin "1") (pinfunction "1_1") (pintype "passive"))
      (node (ref "C45") (pin "1") (pinfunction "1_1") (pintype "passive"))
      (node (ref "C46") (pin "1") (pinfunction "1_1") (pintype "passive"))
      (node (ref "C47") (pin "1") (pinfunction "1_1") (pintype "passive"))
      (node (ref "C48") (pin "1") (pinfunction "1_1") (pintype "passive"))
      (node (ref "C5") (pin "1") (pinfunction "1_1") (pintype "passive"))
      (node (ref "C6") (pin "1") (pinfunction "1_1") (pintype "passive"))
      (node (ref "C7") (pin "1") (pinfunction "1_1") (pintype "passive"))
      (node (ref "C8") (pin "1") (pinfunction "1_1") (pintype "passive"))
      (node (ref "C9") (pin "1") (pinfunction "1_1") (pintype "passive"))
      (node (ref "R3") (pin "1") (pinfunction "1_1") (pintype "passive"))
      (node (ref "U1") (pin "A10") (pinfunction "VSS_A10") (pintype "passive"))
      (node (ref "U1") (pin "A3") (pinfunction "VSS_A3") (pintype "passive"))
      (node (ref "U1") (pin "AB10") (pinfunction "VSS_AB10") (pintype "passive"))
      (node (ref "U1") (pin "AB3") (pinfunction "VSS_AB3") (pintype "passive"))
      (node (ref "U1") (pin "AB5") (pinfunction "VSS_AB5") (pintype "passive"))
      (node (ref "U1") (pin "AB8") (pinfunction "VSS_AB8") (pintype "passive"))
      (node (ref "U1") (pin "C1") (pinfunction "VSS_C1") (pintype "passive"))
      (node (ref "U1") (pin "C12") (pinfunction "VSS_C12") (pintype "passive"))
      (node (ref "U1") (pin "C5") (pinfunction "VSS_C5") (pintype "passive"))
      (node (ref "U1") (pin "C8") (pinfunction "VSS_C8") (pintype "passive"))
      (node (ref "U1") (pin "D11") (pinfunction "VSS_D11") (pintype "passive"))
      (node (ref "U1") (pin "D2") (pinfunction "VSS_D2") (pintype "passive"))
      (node (ref "U1") (pin "D4") (pinfunction "VSS_D4") (pintype "passive"))
      (node (ref "U1") (pin "D9") (pinfunction "VSS_D9") (pintype "passive"))
      (node (ref "U1") (pin "E1") (pinfunction "VSS_E1") (pintype "passive"))
      (node (ref "U1") (pin "E12") (pinfunction "VSS_E12") (pintype "passive"))
      (node (ref "U1") (pin "E5") (pinfunction "VSS_E5") (pintype "passive"))
      (node (ref "U1") (pin "E8") (pinfunction "VSS_E8") (pintype "passive"))
      (node (ref "U1") (pin "G1") (pinfunction "VSS_G1") (pintype "passive"))
      (node (ref "U1") (pin "G10") (pinfunction "VSS_G10") (pintype "passive"))
      (node (ref "U1") (pin "G12") (pinfunction "VSS_G12") (pintype "passive"))
      (node (ref "U1") (pin "G3") (pinfunction "VSS_G3") (pintype "passive"))
      (node (ref "U1") (pin "G5") (pinfunction "VSS_G5") (pintype "passive"))
      (node (ref "U1") (pin "G8") (pinfunction "VSS_G8") (pintype "passive"))
      (node (ref "U1") (pin "J1") (pinfunction "VSS_J1") (pintype "passive"))
      (node (ref "U1") (pin "J10") (pinfunction "VSS_J10") (pintype "passive"))
      (node (ref "U1") (pin "J12") (pinfunction "VSS_J12") (pintype "passive"))
      (node (ref "U1") (pin "J3") (pinfunction "VSS_J3") (pintype "passive"))
      (node (ref "U1") (pin "K11") (pinfunction "VSS_K11") (pintype "passive"))
      (node (ref "U1") (pin "K2") (pinfunction "VSS_K2") (pintype "passive"))
      (node (ref "U1") (pin "K4") (pinfunction "VSS_K4") (pintype "passive"))
      (node (ref "U1") (pin "K9") (pinfunction "VSS_K9") (pintype "passive"))
      (node (ref "U1") (pin "N11") (pinfunction "VSS_N11") (pintype "passive"))
      (node (ref "U1") (pin "N2") (pinfunction "VSS_N2") (pintype "passive"))
      (node (ref "U1") (pin "N4") (pinfunction "VSS_N4") (pintype "passive"))
      (node (ref "U1") (pin "N9") (pinfunction "VSS_N9") (pintype "passive"))
      (node (ref "U1") (pin "P1") (pinfunction "VSS_P1") (pintype "passive"))
      (node (ref "U1") (pin "P10") (pinfunction "VSS_P10") (pintype "passive"))
      (node (ref "U1") (pin "P12") (pinfunction "VSS_P12") (pintype "passive"))
      (node (ref "U1") (pin "P3") (pinfunction "VSS_P3") (pintype "passive"))
      (node (ref "U1") (pin "T1") (pinfunction "VSS_T1") (pintype "passive"))
      (node (ref "U1") (pin "T10") (pinfunction "VSS_T10") (pintype "passive"))
      (node (ref "U1") (pin "T12") (pinfunction "VSS_T12") (pintype "passive"))
      (node (ref "U1") (pin "T3") (pinfunction "VSS_T3") (pintype "passive"))
      (node (ref "U1") (pin "T5") (pinfunction "VSS_T5") (pintype "passive"))
      (node (ref "U1") (pin "T8") (pinfunction "VSS_T8") (pintype "passive"))
      (node (ref "U1") (pin "V1") (pinfunction "VSS_V1") (pintype "passive"))
      (node (ref "U1") (pin "V12") (pinfunction "VSS_V12") (pintype "passive"))
      (node (ref "U1") (pin "V5") (pinfunction "VSS_V5") (pintype "passive"))
      (node (ref "U1") (pin "V8") (pinfunction "VSS_V8") (pintype "passive"))
      (node (ref "U1") (pin "W11") (pinfunction "VSS_W11") (pintype "passive"))
      (node (ref "U1") (pin "W2") (pinfunction "VSS_W2") (pintype "passive"))
      (node (ref "U1") (pin "W4") (pinfunction "VSS_W4") (pintype "passive"))
      (node (ref "U1") (pin "W9") (pinfunction "VSS_W9") (pintype "passive"))
      (node (ref "U1") (pin "Y1") (pinfunction "VSS_Y1") (pintype "passive"))
      (node (ref "U1") (pin "Y12") (pinfunction "VSS_Y12") (pintype "passive"))
      (node (ref "U1") (pin "Y5") (pinfunction "VSS_Y5") (pintype "passive"))
      (node (ref "U1") (pin "Y8") (pinfunction "VSS_Y8") (pintype "passive"))
    )
    (net (code "63") (name "Net-(U1A-ODT_CA_A)") (class "Default")
      (node (ref "R1") (pin "1") (pinfunction "1_1") (pintype "passive"))
      (node (ref "U1") (pin "G2") (pinfunction "ODT_CA_A_G2") (pintype "passive"))
    )
    (net (code "64") (name "Net-(U1A-ODT_CA_B)") (class "Default")
      (node (ref "R3") (pin "2") (pinfunction "2_2") (pintype "passive"))
      (node (ref "U1") (pin "T2") (pinfunction "ODT_CA_B_T2") (pintype "passive"))
    )
    (net (code "65") (name "Net-(U1A-ZQ0)") (class "Default")
      (node (ref "R2") (pin "2") (pinfunction "2_2") (pintype "passive"))
      (node (ref "U1") (pin "A5") (pinfunction "ZQ0_A5") (pintype "passive"))
    )
    (net (code "66") (name "Net-(U1A-ZQ1)") (class "Default")
      (node (ref "R4") (pin "2") (pinfunction "2_2") (pintype "passive"))
      (node (ref "U1") (pin "A8") (pinfunction "ZQ1_A8") (pintype "passive"))
    )
    (net (code "67") (name "VCC1V8_LPDDR4_A") (class "Default")
      (node (ref "C39") (pin "2") (pinfunction "2_2") (pintype "passive"))
      (node (ref "C40") (pin "2") (pinfunction "2_2") (pintype "passive"))
      (node (ref "C41") (pin "2") (pinfunction "2_2") (pintype "passive"))
      (node (ref "C42") (pin "2") (pinfunction "2_2") (pintype "passive"))
      (node (ref "C43") (pin "2") (pinfunction "2_2") (pintype "passive"))
      (node (ref "C44") (pin "2") (pinfunction "2_2") (pintype "passive"))
      (node (ref "C45") (pin "2") (pinfunction "2_2") (pintype "passive"))
      (node (ref "C46") (pin "2") (pinfunction "2_2") (pintype "passive"))
      (node (ref "C47") (pin "2") (pinfunction "2_2") (pintype "passive"))
      (node (ref "C48") (pin "2") (pinfunction "2_2") (pintype "passive"))
      (node (ref "U1") (pin "F1") (pinfunction "VDD1_F1") (pintype "passive"))
      (node (ref "U1") (pin "F12") (pinfunction "VDD1_F12") (pintype "passive"))
      (node (ref "U1") (pin "G4") (pinfunction "VDD1_G4") (pintype "passive"))
      (node (ref "U1") (pin "G9") (pinfunction "VDD1_G9") (pintype "passive"))
      (node (ref "U1") (pin "T4") (pinfunction "VDD1_T4") (pintype "passive"))
      (node (ref "U1") (pin "T9") (pinfunction "VDD1_T9") (pintype "passive"))
      (node (ref "U1") (pin "U1") (pinfunction "VDD1_U1") (pintype "passive"))
      (node (ref "U1") (pin "U12") (pinfunction "VDD1_U12") (pintype "passive"))
    )
    (net (code "68") (name "VCC_DDR") (class "Default")
      (node (ref "C1") (pin "2") (pinfunction "2_2") (pintype "passive"))
      (node (ref "C10") (pin "2") (pinfunction "2_2") (pintype "passive"))
      (node (ref "C11") (pin "2") (pinfunction "2_2") (pintype "passive"))
      (node (ref "C12") (pin "2") (pinfunction "2_2") (pintype "passive"))
      (node (ref "C13") (pin "2") (pinfunction "2_2") (pintype "passive"))
      (node (ref "C14") (pin "2") (pinfunction "2_2") (pintype "passive"))
      (node (ref "C15") (pin "2") (pinfunction "2_2") (pintype "passive"))
      (node (ref "C16") (pin "2") (pinfunction "2_2") (pintype "passive"))
      (node (ref "C17") (pin "2") (pinfunction "2_2") (pintype "passive"))
      (node (ref "C18") (pin "2") (pinfunction "2_2") (pintype "passive"))
      (node (ref "C19") (pin "2") (pinfunction "2_2") (pintype "passive"))
      (node (ref "C2") (pin "2") (pinfunction "2_2") (pintype "passive"))
      (node (ref "C3") (pin "2") (pinfunction "2_2") (pintype "passive"))
      (node (ref "C4") (pin "2") (pinfunction "2_2") (pintype "passive"))
      (node (ref "C5") (pin "2") (pinfunction "2_2") (pintype "passive"))
      (node (ref "C6") (pin "2") (pinfunction "2_2") (pintype "passive"))
      (node (ref "C7") (pin "2") (pinfunction "2_2") (pintype "passive"))
      (node (ref "C8") (pin "2") (pinfunction "2_2") (pintype "passive"))
      (node (ref "C9") (pin "2") (pinfunction "2_2") (pintype "passive"))
      (node (ref "U1") (pin "A4") (pinfunction "VDD2_A4") (pintype "passive"))
      (node (ref "U1") (pin "A9") (pinfunction "VDD2_A9") (pintype "passive"))
      (node (ref "U1") (pin "AB4") (pinfunction "VDD2_AB4") (pintype "passive"))
      (node (ref "U1") (pin "AB9") (pinfunction "VDD2_AB9") (pintype "passive"))
      (node (ref "U1") (pin "F5") (pinfunction "VDD2_F5") (pintype "passive"))
      (node (ref "U1") (pin "F8") (pinfunction "VDD2_F8") (pintype "passive"))
      (node (ref "U1") (pin "H1") (pinfunction "VDD2_H1") (pintype "passive"))
      (node (ref "U1") (pin "H12") (pinfunction "VDD2_H12") (pintype "passive"))
      (node (ref "U1") (pin "H5") (pinfunction "VDD2_H5") (pintype "passive"))
      (node (ref "U1") (pin "H8") (pinfunction "VDD2_H8") (pintype "passive"))
      (node (ref "U1") (pin "K1") (pinfunction "VDD2_K1") (pintype "passive"))
      (node (ref "U1") (pin "K10") (pinfunction "VDD2_K10") (pintype "passive"))
      (node (ref "U1") (pin "K12") (pinfunction "VDD2_K12") (pintype "passive"))
      (node (ref "U1") (pin "K3") (pinfunction "VDD2_K3") (pintype "passive"))
      (node (ref "U1") (pin "N1") (pinfunction "VDD2_N1") (pintype "passive"))
      (node (ref "U1") (pin "N10") (pinfunction "VDD2_N10") (pintype "passive"))
      (node (ref "U1") (pin "N12") (pinfunction "VDD2_N12") (pintype "passive"))
      (node (ref "U1") (pin "N3") (pinfunction "VDD2_N3") (pintype "passive"))
      (node (ref "U1") (pin "R1") (pinfunction "VDD2_R1") (pintype "passive"))
      (node (ref "U1") (pin "R12") (pinfunction "VDD2_R12") (pintype "passive"))
      (node (ref "U1") (pin "R5") (pinfunction "VDD2_R5") (pintype "passive"))
      (node (ref "U1") (pin "R8") (pinfunction "VDD2_R8") (pintype "passive"))
      (node (ref "U1") (pin "U5") (pinfunction "VDD2_U5") (pintype "passive"))
      (node (ref "U1") (pin "U8") (pinfunction "VDD2_U8") (pintype "passive"))
    )
    (net (code "69") (name "VCC_DDRC") (class "Default")
      (node (ref "C20") (pin "2") (pinfunction "2_2") (pintype "passive"))
      (node (ref "C21") (pin "2") (pinfunction "2_2") (pintype "passive"))
      (node (ref "C22") (pin "2") (pinfunction "2_2") (pintype "passive"))
      (node (ref "C23") (pin "2") (pinfunction "2_2") (pintype "passive"))
      (node (ref "C24") (pin "2") (pinfunction "2_2") (pintype "passive"))
      (node (ref "C25") (pin "2") (pinfunction "2_2") (pintype "passive"))
      (node (ref "C26") (pin "2") (pinfunction "2_2") (pintype "passive"))
      (node (ref "C27") (pin "2") (pinfunction "2_2") (pintype "passive"))
      (node (ref "C28") (pin "2") (pinfunction "2_2") (pintype "passive"))
      (node (ref "C29") (pin "2") (pinfunction "2_2") (pintype "passive"))
      (node (ref "C30") (pin "2") (pinfunction "2_2") (pintype "passive"))
      (node (ref "C31") (pin "2") (pinfunction "2_2") (pintype "passive"))
      (node (ref "C32") (pin "2") (pinfunction "2_2") (pintype "passive"))
      (node (ref "C33") (pin "2") (pinfunction "2_2") (pintype "passive"))
      (node (ref "C34") (pin "2") (pinfunction "2_2") (pintype "passive"))
      (node (ref "C35") (pin "2") (pinfunction "2_2") (pintype "passive"))
      (node (ref "C36") (pin "2") (pinfunction "2_2") (pintype "passive"))
      (node (ref "C37") (pin "2") (pinfunction "2_2") (pintype "passive"))
      (node (ref "C38") (pin "2") (pinfunction "2_2") (pintype "passive"))
      (node (ref "U1") (pin "AA10") (pinfunction "VDDQ_AA10") (pintype "passive"))
      (node (ref "U1") (pin "AA3") (pinfunction "VDDQ_AA3") (pintype "passive"))
      (node (ref "U1") (pin "AA5") (pinfunction "VDDQ_AA5") (pintype "passive"))
      (node (ref "U1") (pin "AA8") (pinfunction "VDDQ_AA8") (pintype "passive"))
      (node (ref "U1") (pin "B10") (pinfunction "VDDQ_B10") (pintype "passive"))
      (node (ref "U1") (pin "B3") (pinfunction "VDDQ_B3") (pintype "passive"))
      (node (ref "U1") (pin "B5") (pinfunction "VDDQ_B5") (pintype "passive"))
      (node (ref "U1") (pin "B8") (pinfunction "VDDQ_B8") (pintype "passive"))
      (node (ref "U1") (pin "D1") (pinfunction "VDDQ_D1") (pintype "passive"))
      (node (ref "U1") (pin "D12") (pinfunction "VDDQ_D12") (pintype "passive"))
      (node (ref "U1") (pin "D5") (pinfunction "VDDQ_D5") (pintype "passive"))
      (node (ref "U1") (pin "D8") (pinfunction "VDDQ_D8") (pintype "passive"))
      (node (ref "U1") (pin "F10") (pinfunction "VDDQ_F10") (pintype "passive"))
      (node (ref "U1") (pin "F3") (pinfunction "VDDQ_F3") (pintype "passive"))
      (node (ref "U1") (pin "U10") (pinfunction "VDDQ_U10") (pintype "passive"))
      (node (ref "U1") (pin "U3") (pinfunction "VDDQ_U3") (pintype "passive"))
      (node (ref "U1") (pin "W1") (pinfunction "VDDQ_W1") (pintype "passive"))
      (node (ref "U1") (pin "W12") (pinfunction "VDDQ_W12") (pintype "passive"))
      (node (ref "U1") (pin "W5") (pinfunction "VDDQ_W5") (pintype "passive"))
      (node (ref "U1") (pin "W8") (pinfunction "VDDQ_W8") (pintype "passive"))
    )
    (net (code "70") (name "VDDQ") (class "Default")
      (node (ref "R1") (pin "2") (pinfunction "2_2") (pintype "passive"))
      (node (ref "R2") (pin "1") (pinfunction "1_1") (pintype "passive"))
      (node (ref "R4") (pin "1") (pinfunction "1_1") (pintype "passive"))
    )
    (net (code "71") (name "unconnected-(U1B-DNU1-PadA1)") (class "Default")
      (node (ref "U1") (pin "A1") (pinfunction "DNU1_A1") (pintype "passive+no_connect"))
    )
    (net (code "72") (name "unconnected-(U1B-DNU2-PadA2)") (class "Default")
      (node (ref "U1") (pin "A2") (pinfunction "DNU2_A2") (pintype "passive+no_connect"))
    )
    (net (code "73") (name "unconnected-(U1B-DNU3-PadA11)") (class "Default")
      (node (ref "U1") (pin "A11") (pinfunction "DNU3_A11") (pintype "passive+no_connect"))
    )
    (net (code "74") (name "unconnected-(U1B-DNU4-PadA12)") (class "Default")
      (node (ref "U1") (pin "A12") (pinfunction "DNU4_A12") (pintype "passive+no_connect"))
    )
    (net (code "75") (name "unconnected-(U1B-DNU5-PadB1)") (class "Default")
      (node (ref "U1") (pin "B1") (pinfunction "DNU5_B1") (pintype "passive+no_connect"))
    )
    (net (code "76") (name "unconnected-(U1B-DNU6-PadB12)") (class "Default")
      (node (ref "U1") (pin "B12") (pinfunction "DNU6_B12") (pintype "passive+no_connect"))
    )
    (net (code "77") (name "unconnected-(U1B-DNU7-PadAA1)") (class "Default")
      (node (ref "U1") (pin "AA1") (pinfunction "DNU7_AA1") (pintype "passive+no_connect"))
    )
    (net (code "78") (name "unconnected-(U1B-DNU8-PadAA12)") (class "Default")
      (node (ref "U1") (pin "AA12") (pinfunction "DNU8_AA12") (pintype "passive+no_connect"))
    )
    (net (code "79") (name "unconnected-(U1B-DNU9-PadAB1)") (class "Default")
      (node (ref "U1") (pin "AB1") (pinfunction "DNU9_AB1") (pintype "passive+no_connect"))
    )
    (net (code "80") (name "unconnected-(U1B-DNU10-PadAB2)") (class "Default")
      (node (ref "U1") (pin "AB2") (pinfunction "DNU10_AB2") (pintype "passive+no_connect"))
    )
    (net (code "81") (name "unconnected-(U1B-DNU11-PadAB11)") (class "Default")
      (node (ref "U1") (pin "AB11") (pinfunction "DNU11_AB11") (pintype "passive+no_connect"))
    )
    (net (code "82") (name "unconnected-(U1B-DNU12-PadAB12)") (class "Default")
      (node (ref "U1") (pin "AB12") (pinfunction "DNU12_AB12") (pintype "passive+no_connect"))
    )
    (net (code "83") (name "unconnected-(U1B-DNU13-PadK8)") (class "Default")
      (node (ref "U1") (pin "K8") (pinfunction "DNU13_K8") (pintype "passive+no_connect"))
    )
    (net (code "84") (name "unconnected-(U1B-DNU14-PadN5)") (class "Default")
      (node (ref "U1") (pin "N5") (pinfunction "DNU14_N5") (pintype "passive+no_connect"))
    )
    (net (code "85") (name "unconnected-(U1B-DNU15-PadK5)") (class "Default")
      (node (ref "U1") (pin "K5") (pinfunction "DNU15_K5") (pintype "passive+no_connect"))
    )
    (net (code "86") (name "unconnected-(U1B-DNU16-PadG11)") (class "Default")
      (node (ref "U1") (pin "G11") (pinfunction "DNU16_G11") (pintype "passive+no_connect"))
    )
    (net (code "87") (name "unconnected-(U1B-DNU17-PadN8)") (class "Default")
      (node (ref "U1") (pin "N8") (pinfunction "DNU17_N8") (pintype "passive+no_connect"))
    )
  )
)
